# ARM_MCU.net
KiCad netlist of a schematic drawn in Altium Designer
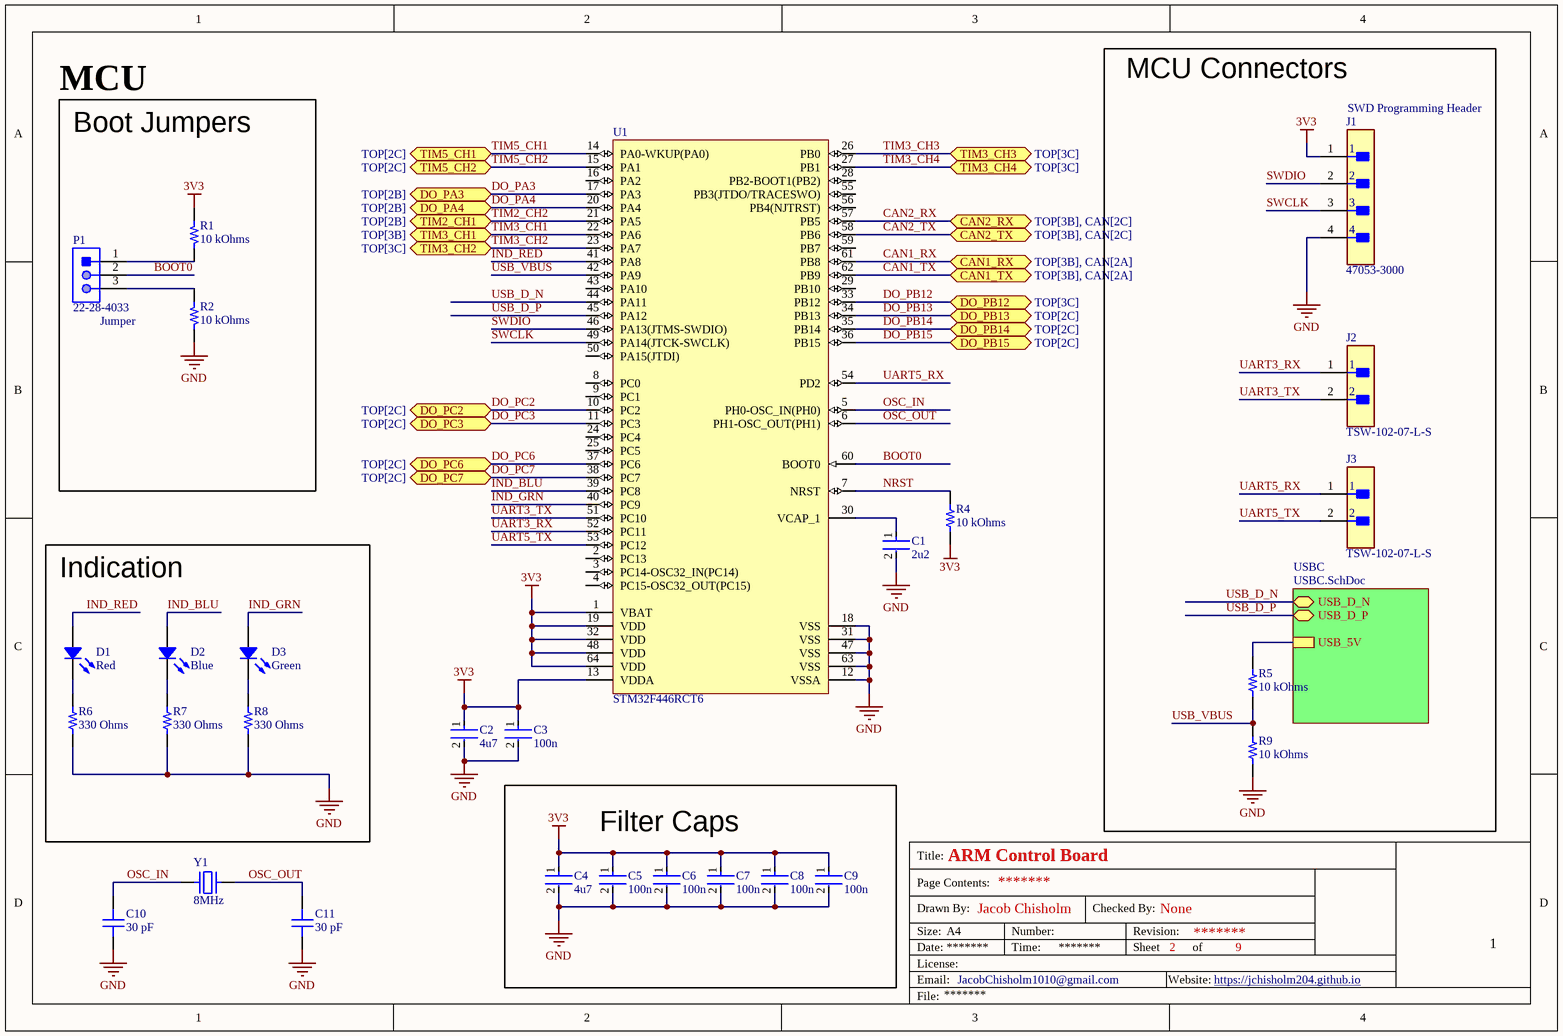
[diagram p0: ARM_MCU.SchDoc]

(export (version "E")
  (design (tool "Eeschema 10.0.6"))
  (components
    (comp (ref "C1")
      (value "2u2")
      (footprint "FP-CL10-IPC_C")
      (description "Cap Ceramic 4.7uF 10V X5R ±10% Pad SMD 0603 +85°C T/R")
      (fields (field (name "TOLERANCE") "10%"))
      (libsource (lib "Altium Content Vault") (part "b4654b650e69147ec39a6b967a45e02"))
    )
    (comp (ref "C2")
      (value "4u7")
      (footprint "FP-CL10-IPC_C")
      (description "Cap Ceramic 4.7uF 10V X5R ±10% Pad SMD 0603 +85°C T/R")
      (fields (field (name "TOLERANCE") "10%"))
      (libsource (lib "Altium Content Vault") (part "b4654b650e69147ec39a6b967a45e02"))
    )
    (comp (ref "C3")
      (value "100n")
      (footprint "FP-CL779-IPC_C")
      (description "Cap Ceramic 100nF 50V X7R ±10% SMD 0402 +125°C Paper T/R")
      (libsource (lib "Altium Content Vault") (part "b4654b650e69147ec39a6b967a45e02"))
    )
    (comp (ref "C4")
      (value "4u7")
      (footprint "FP-CL10-IPC_C")
      (description "Cap Ceramic 4.7uF 10V X5R ±10% Pad SMD 0603 +85°C T/R")
      (fields (field (name "TOLERANCE") "10%"))
      (libsource (lib "Altium Content Vault") (part "b4654b650e69147ec39a6b967a45e02"))
    )
    (comp (ref "C5")
      (value "100n")
      (footprint "FP-CL779-IPC_C")
      (description "Cap Ceramic 100nF 50V X7R ±10% SMD 0402 +125°C Paper T/R")
      (libsource (lib "Altium Content Vault") (part "b4654b650e69147ec39a6b967a45e02"))
    )
    (comp (ref "C6")
      (value "100n")
      (footprint "FP-CL779-IPC_C")
      (description "Cap Ceramic 100nF 50V X7R ±10% SMD 0402 +125°C Paper T/R")
      (libsource (lib "Altium Content Vault") (part "b4654b650e69147ec39a6b967a45e02"))
    )
    (comp (ref "C7")
      (value "100n")
      (footprint "FP-CL779-IPC_C")
      (description "Cap Ceramic 100nF 50V X7R ±10% SMD 0402 +125°C Paper T/R")
      (libsource (lib "Altium Content Vault") (part "b4654b650e69147ec39a6b967a45e02"))
    )
    (comp (ref "C8")
      (value "100n")
      (footprint "FP-CL779-IPC_C")
      (description "Cap Ceramic 100nF 50V X7R ±10% SMD 0402 +125°C Paper T/R")
      (libsource (lib "Altium Content Vault") (part "b4654b650e69147ec39a6b967a45e02"))
    )
    (comp (ref "C9")
      (value "100n")
      (footprint "FP-CL779-IPC_C")
      (description "Cap Ceramic 100nF 50V X7R ±10% SMD 0402 +125°C Paper T/R")
      (libsource (lib "Altium Content Vault") (part "b4654b650e69147ec39a6b967a45e02"))
    )
    (comp (ref "C10")
      (value "30 pF")
      (footprint "CAP 0603_1608")
      (description "CAP CER 30PF 50V C0G/NP0 0603")
      (fields
        (field (name "PART NUMBER") "0603N300J500CT")
        (field (name "MANUFACTURER") "Walsin Technology Corporation")
      )
      (libsource (lib "Celestial Altium Library - altium_library") (part "Capacitor"))
    )
    (comp (ref "C11")
      (value "30 pF")
      (footprint "CAP 0603_1608")
      (description "CAP CER 30PF 50V C0G/NP0 0603")
      (fields
        (field (name "PART NUMBER") "0603N300J500CT")
        (field (name "MANUFACTURER") "Walsin Technology Corporation")
      )
      (libsource (lib "Celestial Altium Library - altium_library") (part "Capacitor"))
    )
    (comp (ref "D1")
      (value "Red")
      (footprint "LED 0603_1608 RED")
      (description "LED RED CLEAR 2SMD")
      (fields
        (field (name "PART NUMBER") "19-213SDRC/S259/TR8")
        (field (name "MANUFACTURER") "Everlight Electronics Co Ltd")
      )
      (libsource (lib "Celestial Altium Library - altium_library") (part "LED"))
    )
    (comp (ref "D2")
      (value "Blue")
      (footprint "LED 0603_1608 BLUE")
      (description "LED BLUE CLEAR 2SMD")
      (fields
        (field (name "PART NUMBER") "19-213SUBC/S400-A5/S208-2/TR8")
        (field (name "MANUFACTURER") "Everlight Electronics Co Ltd")
      )
      (libsource (lib "Celestial Altium Library - altium_library") (part "LED"))
    )
    (comp (ref "D3")
      (value "Green")
      (footprint "LED 0603_1608 GREEN")
      (description "LED GREEN DIFFUSED 0603 SMD")
      (fields (field (name "PART NUMBER") "150060GS55040") (field (name "MANUFACTURER") "Würth Elektronik"))
      (libsource (lib "Celestial Altium Library - altium_library") (part "LED"))
    )
    (comp (ref "J1")
      (value "47053-3000")
      (footprint "FP-47053-3000-MFG")
      (description "CONN HEADER VERT 4POS 2.54MM")
      (libsource (lib "Altium Content Vault") (part "299a8cea1bdcbc3624fe62c390fa72c"))
    )
    (comp (ref "J2")
      (value "TSW-102-07-L-S")
      (footprint "FP-TSW-102-07-L-S-MFG")
      (description "CONN HEADER VERT 2POS 2.54MM")
      (libsource (lib "Altium Content Vault") (part "3bc925449376181038e59eaffc5286c"))
    )
    (comp (ref "J3")
      (value "TSW-102-07-L-S")
      (footprint "FP-TSW-102-07-L-S-MFG")
      (description "CONN HEADER VERT 2POS 2.54MM")
      (libsource (lib "Altium Content Vault") (part "3bc925449376181038e59eaffc5286c"))
    )
    (comp (ref "P1")
      (value "22-28-4033")
      (footprint "MOLX-22-28-4033_V")
      (description "Male Header, Pitch 2.54 mm, 1 x 3 Position, Height 8.38 mm, Tail Length 3.18 mm, RoHS, Bulk")
      (fields (field (name "MANUFACTURER") "Molex"))
      (libsource (lib "Altium Content Vault") (part "CN-1P-M-R3"))
    )
    (comp (ref "R1")
      (value "10 kOhms")
      (footprint "RES 0603_1608")
      (description "P2TC0603 2PPM/C 10K 0,01% N TA")
      (fields
        (field (name "PART NUMBER") "P2TC0603D1002LNTA")
        (field (name "MANUFACTURER") "Vishay Sfernice")
      )
      (libsource (lib "Celestial Altium Library - altium_library") (part "Resistor"))
    )
    (comp (ref "R2")
      (value "10 kOhms")
      (footprint "RES 0603_1608")
      (description "P2TC0603 2PPM/C 10K 0,01% N TA")
      (fields
        (field (name "PART NUMBER") "P2TC0603D1002LNTA")
        (field (name "MANUFACTURER") "Vishay Sfernice")
      )
      (libsource (lib "Celestial Altium Library - altium_library") (part "Resistor"))
    )
    (comp (ref "R4")
      (value "10 kOhms")
      (footprint "RES 0603_1608")
      (description "P2TC0603 2PPM/C 10K 0,01% N TA")
      (fields
        (field (name "PART NUMBER") "P2TC0603D1002LNTA")
        (field (name "MANUFACTURER") "Vishay Sfernice")
      )
      (libsource (lib "Celestial Altium Library - altium_library") (part "Resistor"))
    )
    (comp (ref "R5")
      (value "10 kOhms")
      (footprint "RES 0603_1608")
      (description "1/16 WATTS PRECISION CHIP 10 KIL")
      (fields (field (name "PART NUMBER") "APC0603B10K0N") (field (name "MANUFACTURER") "Ohmite"))
      (libsource (lib "Celestial Altium Library - altium_library") (part "Resistor"))
    )
    (comp (ref "R6")
      (value "330 Ohms")
      (footprint "RES 0603_1608")
      (description "RCC0603 100 330R 1% ET1 E3")
      (fields (field (name "PART NUMBER") "RCC0603330RFKEA") (field (name "MANUFACTURER") "Vishay Dale"))
      (libsource (lib "Celestial Altium Library - altium_library") (part "Resistor"))
    )
    (comp (ref "R7")
      (value "330 Ohms")
      (footprint "RES 0603_1608")
      (description "RCC0603 100 330R 1% ET1 E3")
      (fields (field (name "PART NUMBER") "RCC0603330RFKEA") (field (name "MANUFACTURER") "Vishay Dale"))
      (libsource (lib "Celestial Altium Library - altium_library") (part "Resistor"))
    )
    (comp (ref "R8")
      (value "330 Ohms")
      (footprint "RES 0603_1608")
      (description "RCC0603 100 330R 1% ET1 E3")
      (fields (field (name "PART NUMBER") "RCC0603330RFKEA") (field (name "MANUFACTURER") "Vishay Dale"))
      (libsource (lib "Celestial Altium Library - altium_library") (part "Resistor"))
    )
    (comp (ref "R9")
      (value "10 kOhms")
      (footprint "RES 0603_1608")
      (description "1/16 WATTS PRECISION CHIP 10 KIL")
      (fields (field (name "PART NUMBER") "APC0603B10K0N") (field (name "MANUFACTURER") "Ohmite"))
      (libsource (lib "Celestial Altium Library - altium_library") (part "Resistor"))
    )
    (comp (ref "U1")
      (value "STM32F446RCT6")
      (footprint "STM-LQFP64_L")
      (libsource (lib "Altium Content Vault") (part "MC-ARM-STM32F446-LQFP64"))
    )
    (comp (ref "Y1")
      (value "8MHz")
      (footprint "TXC 9C")
      (description "CRYSTAL 8.0000MHZ 20PF SMD")
      (fields (field (name "PART NUMBER") "9C-8.000MBBK-T") (field (name "MANUFACTURER") "TXC CORPORATION"))
      (libsource (lib "Celestial Altium Library - altium_library") (part "TXC Crystal 9C"))
    )
  )
  (nets
    (net (code "1") (name "/BOOT0") (class "Default")
      (node (ref "P1") (pin "2") (pinfunction "2_2") (pintype "passive"))
      (node (ref "U1") (pin "60") (pinfunction "BOOT0_60") (pintype "input"))
    )
    (net (code "2") (name "/CAN1_RX") (class "Default")
      (node (ref "U1") (pin "61") (pinfunction "PB8_61") (pintype "bidirectional"))
    )
    (net (code "3") (name "/CAN1_TX") (class "Default")
      (node (ref "U1") (pin "62") (pinfunction "PB9_62") (pintype "bidirectional"))
    )
    (net (code "4") (name "/CAN2_RX") (class "Default")
      (node (ref "U1") (pin "57") (pinfunction "PB5_57") (pintype "bidirectional"))
    )
    (net (code "5") (name "/CAN2_TX") (class "Default")
      (node (ref "U1") (pin "58") (pinfunction "PB6_58") (pintype "bidirectional"))
    )
    (net (code "6") (name "/DO_PA3") (class "Default")
      (node (ref "U1") (pin "17") (pinfunction "PA3_17") (pintype "bidirectional"))
    )
    (net (code "7") (name "/DO_PA4") (class "Default")
      (node (ref "U1") (pin "20") (pinfunction "PA4_20") (pintype "bidirectional"))
    )
    (net (code "8") (name "/DO_PB12") (class "Default")
      (node (ref "U1") (pin "33") (pinfunction "PB12_33") (pintype "bidirectional"))
    )
    (net (code "9") (name "/DO_PB13") (class "Default")
      (node (ref "U1") (pin "34") (pinfunction "PB13_34") (pintype "bidirectional"))
    )
    (net (code "10") (name "/DO_PB14") (class "Default")
      (node (ref "U1") (pin "35") (pinfunction "PB14_35") (pintype "bidirectional"))
    )
    (net (code "11") (name "/DO_PB15") (class "Default")
      (node (ref "U1") (pin "36") (pinfunction "PB15_36") (pintype "bidirectional"))
    )
    (net (code "12") (name "/DO_PC2") (class "Default")
      (node (ref "U1") (pin "10") (pinfunction "PC2_10") (pintype "bidirectional"))
    )
    (net (code "13") (name "/DO_PC3") (class "Default")
      (node (ref "U1") (pin "11") (pinfunction "PC3_11") (pintype "bidirectional"))
    )
    (net (code "14") (name "/DO_PC6") (class "Default")
      (node (ref "U1") (pin "37") (pinfunction "PC6_37") (pintype "bidirectional"))
    )
    (net (code "15") (name "/DO_PC7") (class "Default")
      (node (ref "U1") (pin "38") (pinfunction "PC7_38") (pintype "bidirectional"))
    )
    (net (code "16") (name "/IND_BLU") (class "Default")
      (node (ref "D2") (pin "1") (pinfunction "1_1") (pintype "passive"))
      (node (ref "U1") (pin "39") (pinfunction "PC8_39") (pintype "bidirectional"))
    )
    (net (code "17") (name "/IND_GRN") (class "Default")
      (node (ref "D3") (pin "1") (pinfunction "1_1") (pintype "passive"))
      (node (ref "U1") (pin "40") (pinfunction "PC9_40") (pintype "bidirectional"))
    )
    (net (code "18") (name "/IND_RED") (class "Default")
      (node (ref "D1") (pin "1") (pinfunction "1_1") (pintype "passive"))
      (node (ref "U1") (pin "41") (pinfunction "PA8_41") (pintype "bidirectional"))
    )
    (net (code "19") (name "/NRST") (class "Default")
      (node (ref "R4") (pin "2") (pinfunction "2_2") (pintype "passive"))
      (node (ref "U1") (pin "7") (pinfunction "NRST_7") (pintype "bidirectional"))
    )
    (net (code "20") (name "/OSC_IN") (class "Default")
      (node (ref "C10") (pin "2") (pinfunction "2_2") (pintype "passive"))
      (node (ref "U1") (pin "5") (pinfunction "PH0-OSC_IN(PH0)_5") (pintype "bidirectional"))
      (node (ref "Y1") (pin "1") (pinfunction "1_1") (pintype "passive"))
    )
    (net (code "21") (name "/OSC_OUT") (class "Default")
      (node (ref "C11") (pin "2") (pinfunction "2_2") (pintype "passive"))
      (node (ref "U1") (pin "6") (pinfunction "PH1-OSC_OUT(PH1)_6") (pintype "bidirectional"))
      (node (ref "Y1") (pin "2") (pinfunction "2_2") (pintype "passive"))
    )
    (net (code "22") (name "/SWCLK") (class "Default")
      (node (ref "J1") (pin "3") (pinfunction "3_3") (pintype "passive"))
      (node (ref "U1") (pin "49") (pinfunction "PA14(JTCK-SWCLK)_49") (pintype "bidirectional"))
    )
    (net (code "23") (name "/SWDIO") (class "Default")
      (node (ref "J1") (pin "2") (pinfunction "2_2") (pintype "passive"))
      (node (ref "U1") (pin "46") (pinfunction "PA13(JTMS-SWDIO)_46") (pintype "bidirectional"))
    )
    (net (code "24") (name "/TIM2_CH2") (class "Default")
      (node (ref "U1") (pin "21") (pinfunction "PA5_21") (pintype "bidirectional"))
    )
    (net (code "25") (name "/TIM3_CH1") (class "Default")
      (node (ref "U1") (pin "22") (pinfunction "PA6_22") (pintype "bidirectional"))
    )
    (net (code "26") (name "/TIM3_CH2") (class "Default")
      (node (ref "U1") (pin "23") (pinfunction "PA7_23") (pintype "bidirectional"))
    )
    (net (code "27") (name "/TIM3_CH3") (class "Default")
      (node (ref "U1") (pin "26") (pinfunction "PB0_26") (pintype "bidirectional"))
    )
    (net (code "28") (name "/TIM3_CH4") (class "Default")
      (node (ref "U1") (pin "27") (pinfunction "PB1_27") (pintype "bidirectional"))
    )
    (net (code "29") (name "/TIM5_CH1") (class "Default")
      (node (ref "U1") (pin "14") (pinfunction "PA0-WKUP(PA0)_14") (pintype "bidirectional"))
    )
    (net (code "30") (name "/TIM5_CH2") (class "Default")
      (node (ref "U1") (pin "15") (pinfunction "PA1_15") (pintype "bidirectional"))
    )
    (net (code "31") (name "/UART3_RX") (class "Default")
      (node (ref "J2") (pin "1") (pinfunction "1_1") (pintype "passive"))
      (node (ref "U1") (pin "52") (pinfunction "PC11_52") (pintype "bidirectional"))
    )
    (net (code "32") (name "/UART3_TX") (class "Default")
      (node (ref "J2") (pin "2") (pinfunction "2_2") (pintype "passive"))
      (node (ref "U1") (pin "51") (pinfunction "PC10_51") (pintype "bidirectional"))
    )
    (net (code "33") (name "/UART5_RX") (class "Default")
      (node (ref "J3") (pin "1") (pinfunction "1_1") (pintype "passive"))
      (node (ref "U1") (pin "54") (pinfunction "PD2_54") (pintype "bidirectional"))
    )
    (net (code "34") (name "/UART5_TX") (class "Default")
      (node (ref "J3") (pin "2") (pinfunction "2_2") (pintype "passive"))
      (node (ref "U1") (pin "53") (pinfunction "PC12_53") (pintype "bidirectional"))
    )
    (net (code "35") (name "/USB_5V") (class "Default")
      (node (ref "R5") (pin "2") (pinfunction "2_2") (pintype "passive"))
    )
    (net (code "36") (name "/USB_D_N") (class "Default")
      (node (ref "U1") (pin "44") (pinfunction "PA11_44") (pintype "bidirectional"))
    )
    (net (code "37") (name "/USB_D_P") (class "Default")
      (node (ref "U1") (pin "45") (pinfunction "PA12_45") (pintype "bidirectional"))
    )
    (net (code "38") (name "/USB_VBUS") (class "Default")
      (node (ref "R5") (pin "1") (pinfunction "1_1") (pintype "passive"))
      (node (ref "R9") (pin "2") (pinfunction "2_2") (pintype "passive"))
      (node (ref "U1") (pin "42") (pinfunction "PA9_42") (pintype "bidirectional"))
    )
    (net (code "39") (name "3V3") (class "Default")
      (node (ref "C2") (pin "1") (pinfunction "1_1") (pintype "passive"))
      (node (ref "C3") (pin "1") (pinfunction "1_1") (pintype "passive"))
      (node (ref "C4") (pin "1") (pinfunction "1_1") (pintype "passive"))
      (node (ref "C5") (pin "1") (pinfunction "1_1") (pintype "passive"))
      (node (ref "C6") (pin "1") (pinfunction "1_1") (pintype "passive"))
      (node (ref "C7") (pin "1") (pinfunction "1_1") (pintype "passive"))
      (node (ref "C8") (pin "1") (pinfunction "1_1") (pintype "passive"))
      (node (ref "C9") (pin "1") (pinfunction "1_1") (pintype "passive"))
      (node (ref "J1") (pin "1") (pinfunction "1_1") (pintype "passive"))
      (node (ref "R1") (pin "1") (pinfunction "1_1") (pintype "passive"))
      (node (ref "R4") (pin "1") (pinfunction "1_1") (pintype "passive"))
      (node (ref "U1") (pin "1") (pinfunction "VBAT_1") (pintype "power_in"))
      (node (ref "U1") (pin "13") (pinfunction "VDDA_13") (pintype "power_in"))
      (node (ref "U1") (pin "19") (pinfunction "VDD_19") (pintype "power_in"))
      (node (ref "U1") (pin "32") (pinfunction "VDD_32") (pintype "power_in"))
      (node (ref "U1") (pin "48") (pinfunction "VDD_48") (pintype "power_in"))
      (node (ref "U1") (pin "64") (pinfunction "VDD_64") (pintype "power_in"))
    )
    (net (code "40") (name "GND") (class "Default")
      (node (ref "C1") (pin "2") (pinfunction "2_2") (pintype "passive"))
      (node (ref "C10") (pin "1") (pinfunction "1_1") (pintype "passive"))
      (node (ref "C11") (pin "1") (pinfunction "1_1") (pintype "passive"))
      (node (ref "C2") (pin "2") (pinfunction "2_2") (pintype "passive"))
      (node (ref "C3") (pin "2") (pinfunction "2_2") (pintype "passive"))
      (node (ref "C4") (pin "2") (pinfunction "2_2") (pintype "passive"))
      (node (ref "C5") (pin "2") (pinfunction "2_2") (pintype "passive"))
      (node (ref "C6") (pin "2") (pinfunction "2_2") (pintype "passive"))
      (node (ref "C7") (pin "2") (pinfunction "2_2") (pintype "passive"))
      (node (ref "C8") (pin "2") (pinfunction "2_2") (pintype "passive"))
      (node (ref "C9") (pin "2") (pinfunction "2_2") (pintype "passive"))
      (node (ref "J1") (pin "4") (pinfunction "4_4") (pintype "passive"))
      (node (ref "R2") (pin "1") (pinfunction "1_1") (pintype "passive"))
      (node (ref "R6") (pin "1") (pinfunction "1_1") (pintype "passive"))
      (node (ref "R7") (pin "1") (pinfunction "1_1") (pintype "passive"))
      (node (ref "R8") (pin "1") (pinfunction "1_1") (pintype "passive"))
      (node (ref "R9") (pin "1") (pinfunction "1_1") (pintype "passive"))
      (node (ref "U1") (pin "12") (pinfunction "VSSA_12") (pintype "power_in"))
      (node (ref "U1") (pin "18") (pinfunction "VSS_18") (pintype "power_in"))
      (node (ref "U1") (pin "31") (pinfunction "VSS_31") (pintype "power_in"))
      (node (ref "U1") (pin "47") (pinfunction "VSS_47") (pintype "power_in"))
      (node (ref "U1") (pin "63") (pinfunction "VSS_63") (pintype "power_in"))
    )
    (net (code "41") (name "Net-(D1-Pad2)") (class "Default")
      (node (ref "D1") (pin "2") (pinfunction "2_2") (pintype "passive"))
      (node (ref "R6") (pin "2") (pinfunction "2_2") (pintype "passive"))
    )
    (net (code "42") (name "Net-(D2-Pad2)") (class "Default")
      (node (ref "D2") (pin "2") (pinfunction "2_2") (pintype "passive"))
      (node (ref "R7") (pin "2") (pinfunction "2_2") (pintype "passive"))
    )
    (net (code "43") (name "Net-(D3-Pad2)") (class "Default")
      (node (ref "D3") (pin "2") (pinfunction "2_2") (pintype "passive"))
      (node (ref "R8") (pin "2") (pinfunction "2_2") (pintype "passive"))
    )
    (net (code "44") (name "Net-(P1-Pad1)") (class "Default")
      (node (ref "P1") (pin "1") (pinfunction "1_1") (pintype "passive"))
      (node (ref "R1") (pin "2") (pinfunction "2_2") (pintype "passive"))
    )
    (net (code "45") (name "Net-(P1-Pad3)") (class "Default")
      (node (ref "P1") (pin "3") (pinfunction "3_3") (pintype "passive"))
      (node (ref "R2") (pin "2") (pinfunction "2_2") (pintype "passive"))
    )
    (net (code "46") (name "Net-(U1-VCAP_1)") (class "Default")
      (node (ref "C1") (pin "1") (pinfunction "1_1") (pintype "passive"))
      (node (ref "U1") (pin "30") (pinfunction "VCAP_1_30") (pintype "passive"))
    )
    (net (code "47") (name "unconnected-(U1-PA2-Pad16)") (class "Default")
      (node (ref "U1") (pin "16") (pinfunction "PA2_16") (pintype "bidirectional"))
    )
    (net (code "48") (name "unconnected-(U1-PA10-Pad43)") (class "Default")
      (node (ref "U1") (pin "43") (pinfunction "PA10_43") (pintype "bidirectional"))
    )
    (net (code "49") (name "unconnected-(U1-PA15(JTDI)-Pad50)") (class "Default")
      (node (ref "U1") (pin "50") (pinfunction "PA15(JTDI)_50") (pintype "bidirectional"))
    )
    (net (code "50") (name "unconnected-(U1-PB2-BOOT1(PB2)-Pad28)") (class "Default")
      (node (ref "U1") (pin "28") (pinfunction "PB2-BOOT1(PB2)_28") (pintype "bidirectional"))
    )
    (net (code "51") (name "unconnected-(U1-PB3(JTDO{slash}TRACESWO)-Pad55)") (class "Default")
      (node (ref "U1") (pin "55") (pinfunction "PB3(JTDO/TRACESWO)_55") (pintype "bidirectional"))
    )
    (net (code "52") (name "unconnected-(U1-PB4(NJTRST)-Pad56)") (class "Default")
      (node (ref "U1") (pin "56") (pinfunction "PB4(NJTRST)_56") (pintype "bidirectional"))
    )
    (net (code "53") (name "unconnected-(U1-PB7-Pad59)") (class "Default")
      (node (ref "U1") (pin "59") (pinfunction "PB7_59") (pintype "bidirectional"))
    )
    (net (code "54") (name "unconnected-(U1-PB10-Pad29)") (class "Default")
      (node (ref "U1") (pin "29") (pinfunction "PB10_29") (pintype "bidirectional"))
    )
    (net (code "55") (name "unconnected-(U1-PC0-Pad8)") (class "Default")
      (node (ref "U1") (pin "8") (pinfunction "PC0_8") (pintype "bidirectional"))
    )
    (net (code "56") (name "unconnected-(U1-PC1-Pad9)") (class "Default")
      (node (ref "U1") (pin "9") (pinfunction "PC1_9") (pintype "bidirectional"))
    )
    (net (code "57") (name "unconnected-(U1-PC4-Pad24)") (class "Default")
      (node (ref "U1") (pin "24") (pinfunction "PC4_24") (pintype "bidirectional"))
    )
    (net (code "58") (name "unconnected-(U1-PC5-Pad25)") (class "Default")
      (node (ref "U1") (pin "25") (pinfunction "PC5_25") (pintype "bidirectional"))
    )
    (net (code "59") (name "unconnected-(U1-PC13-Pad2)") (class "Default")
      (node (ref "U1") (pin "2") (pinfunction "PC13_2") (pintype "bidirectional"))
    )
    (net (code "60") (name "unconnected-(U1-PC14-OSC32_IN(PC14)-Pad3)") (class "Default")
      (node (ref "U1") (pin "3") (pinfunction "PC14-OSC32_IN(PC14)_3") (pintype "bidirectional"))
    )
    (net (code "61") (name "unconnected-(U1-PC15-OSC32_OUT(PC15)-Pad4)") (class "Default")
      (node (ref "U1") (pin "4") (pinfunction "PC15-OSC32_OUT(PC15)_4") (pintype "bidirectional"))
    )
  )
)
